# alexandru_ariton.net
KiCad netlist of a schematic drawn in EAGLE
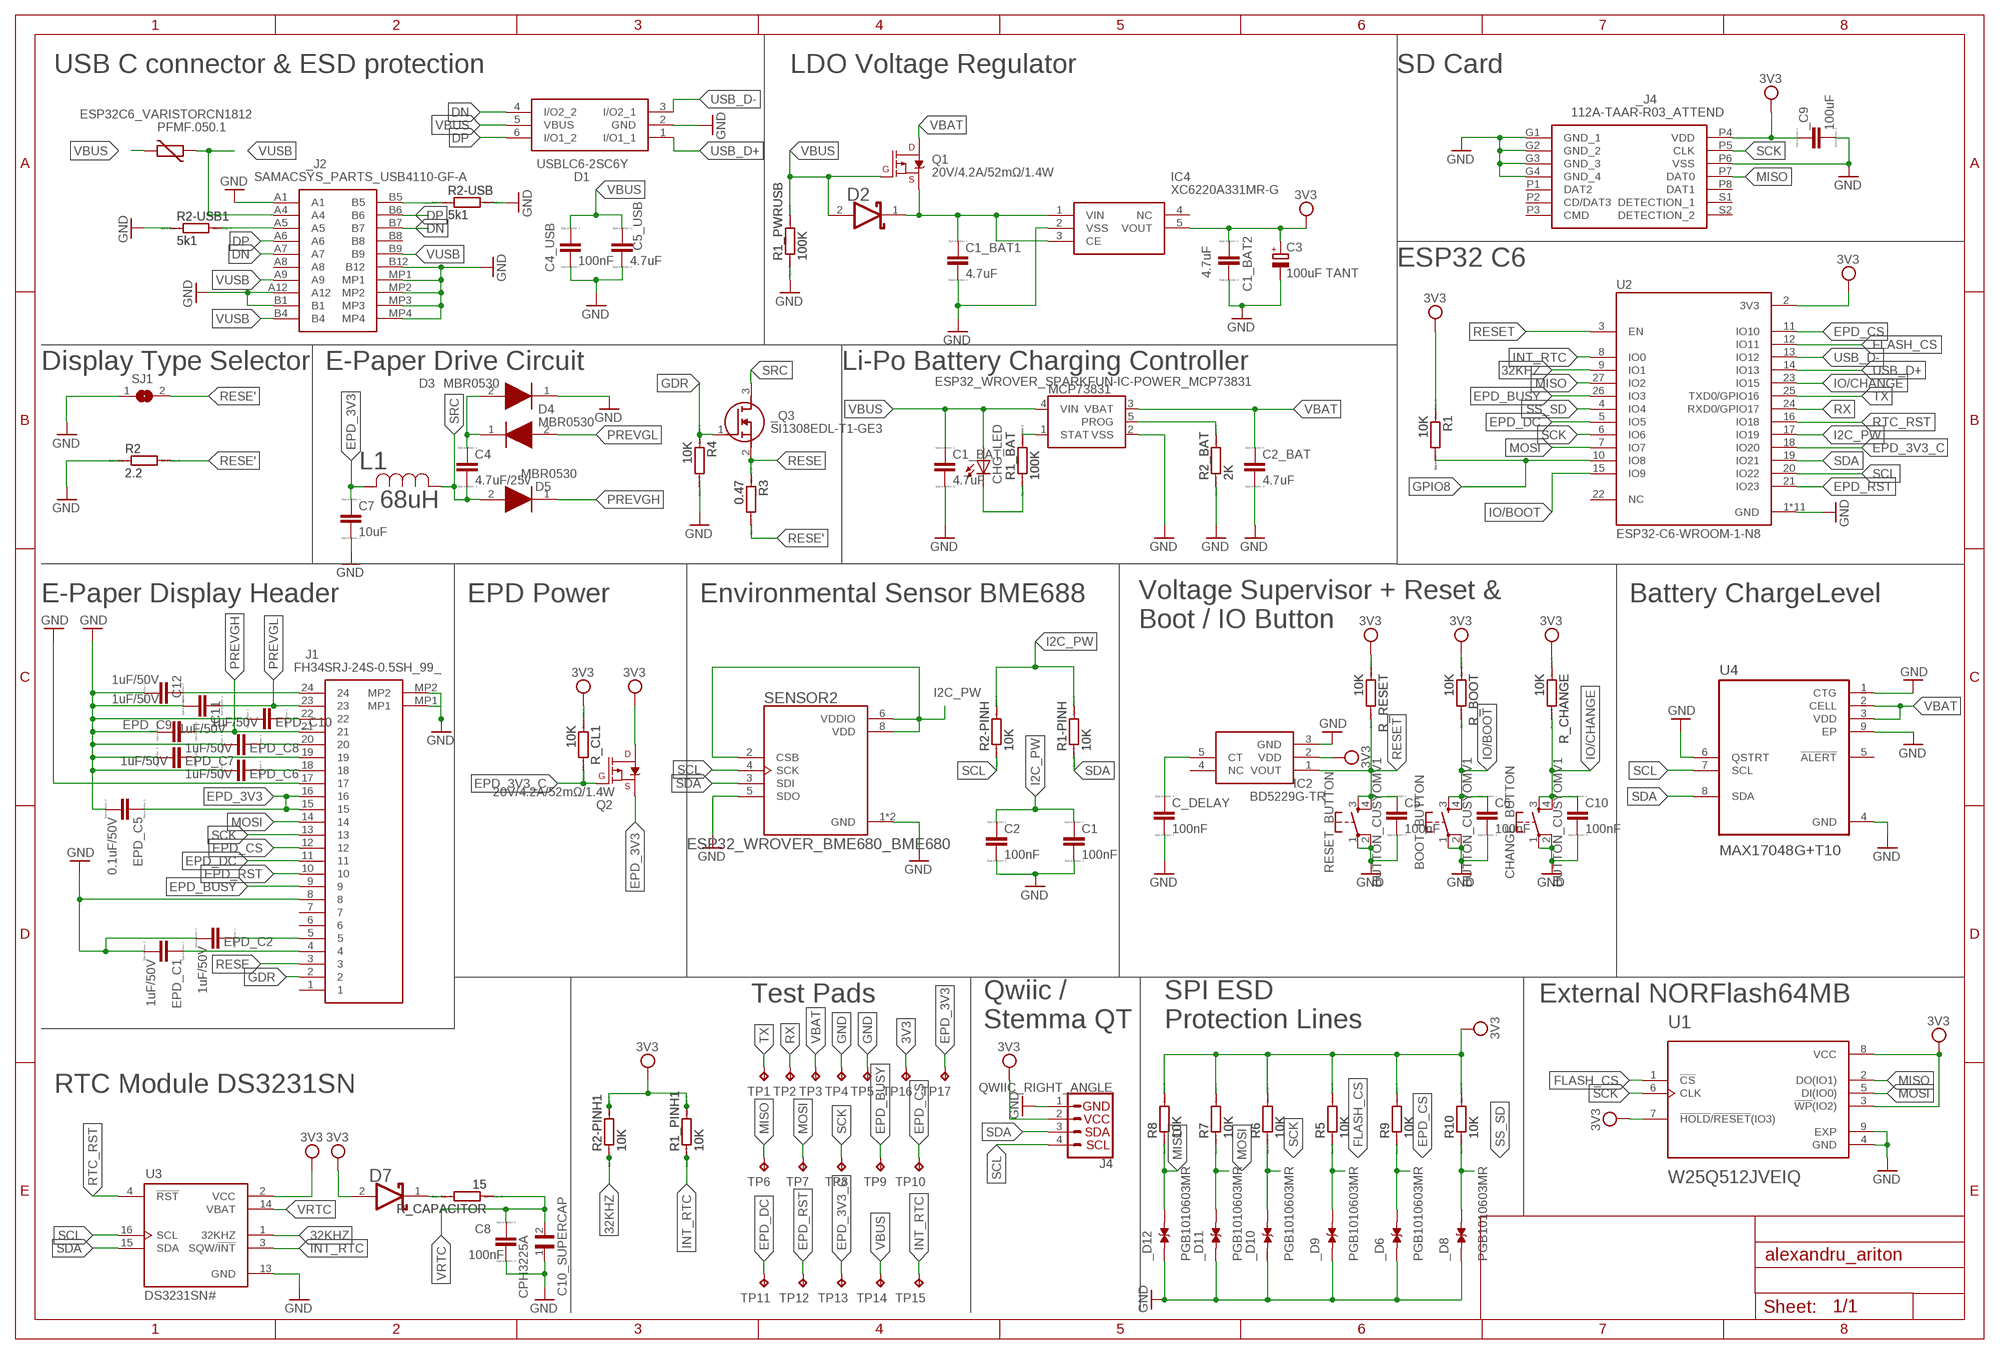
[diagram p0: schematic, sheet 1]

(export (version "E")
  (design (tool "Eeschema 10.0.6"))
  (components
    (comp (ref "BOOT_BUTTON")
      (value "BUTTON_CUSYOMV1")
      (footprint "eagle-import:MYBUTTON")
      (libsource (lib "eagle-import") (part "BUTTON_CUSYOMV1"))
    )
    (comp (ref "C1")
      (value "100nF")
      (footprint "eagle-import:EAGLE-LTSPICE_C0402")
      (libsource (lib "eagle-import") (part "EAGLE-LTSPICE_CC0402"))
    )
    (comp (ref "C1_BAT")
      (value "4.7uF")
      (footprint "eagle-import:EAGLE-LTSPICE_C0402")
      (libsource (lib "eagle-import") (part "EAGLE-LTSPICE_CC0402"))
    )
    (comp (ref "C1_BAT1")
      (value "4.7uF")
      (footprint "eagle-import:EAGLE-LTSPICE_C0402")
      (libsource (lib "eagle-import") (part "EAGLE-LTSPICE_CC0402"))
    )
    (comp (ref "C1_BAT2")
      (value "4.7uF")
      (footprint "eagle-import:EAGLE-LTSPICE_C0402")
      (libsource (lib "eagle-import") (part "EAGLE-LTSPICE_CC0402"))
    )
    (comp (ref "C2")
      (value "100nF")
      (footprint "eagle-import:EAGLE-LTSPICE_C0402")
      (libsource (lib "eagle-import") (part "EAGLE-LTSPICE_CC0402"))
    )
    (comp (ref "C2_BAT")
      (value "4.7uF")
      (footprint "eagle-import:EAGLE-LTSPICE_C0402")
      (libsource (lib "eagle-import") (part "EAGLE-LTSPICE_CC0402"))
    )
    (comp (ref "C3")
      (value "100uF TANT")
      (footprint "eagle-import:RCL_CT3528")
      (libsource (lib "eagle-import") (part "RCL_CPOL-EUCT3528"))
    )
    (comp (ref "C4")
      (value "4.7uF/25v")
      (footprint "eagle-import:EAGLE-LTSPICE_C0402")
      (libsource (lib "eagle-import") (part "EAGLE-LTSPICE_CC0402"))
    )
    (comp (ref "C4_USB")
      (value "100nF")
      (footprint "eagle-import:EAGLE-LTSPICE_C0402")
      (libsource (lib "eagle-import") (part "EAGLE-LTSPICE_CC0402"))
    )
    (comp (ref "C5")
      (value "100nF")
      (footprint "eagle-import:ESP32_WROVER_EAGLE-LTSPICE_C0402")
      (libsource (lib "eagle-import") (part "ESP32_WROVER_EAGLE-LTSPICE_CC0402"))
    )
    (comp (ref "C5_USB")
      (value "4.7uF")
      (footprint "eagle-import:EAGLE-LTSPICE_C0402")
      (libsource (lib "eagle-import") (part "EAGLE-LTSPICE_CC0402"))
    )
    (comp (ref "C6")
      (value "100nF")
      (footprint "eagle-import:ESP32_WROVER_EAGLE-LTSPICE_C0402")
      (libsource (lib "eagle-import") (part "ESP32_WROVER_EAGLE-LTSPICE_CC0402"))
    )
    (comp (ref "C7")
      (value "10uF")
      (footprint "eagle-import:EAGLE-LTSPICE_C0402")
      (libsource (lib "eagle-import") (part "EAGLE-LTSPICE_CC0402"))
    )
    (comp (ref "C8")
      (value "100nF")
      (footprint "eagle-import:EAGLE-LTSPICE_C0402")
      (libsource (lib "eagle-import") (part "EAGLE-LTSPICE_CC0402"))
    )
    (comp (ref "C10")
      (value "100nF")
      (footprint "eagle-import:ESP32_WROVER_EAGLE-LTSPICE_C0402")
      (libsource (lib "eagle-import") (part "ESP32_WROVER_EAGLE-LTSPICE_CC0402"))
    )
    (comp (ref "C10_SUPERCAP")
      (value "CPH3225A")
      (footprint "eagle-import:CAPCP3225X100N")
      (fields (field (name "MF") "Seiko Instruments"))
      (libsource (lib "eagle-import") (part "CPH3225A"))
    )
    (comp (ref "C11")
      (value "1uF/50V")
      (footprint "eagle-import:EAGLE-LTSPICE_C0402")
      (libsource (lib "eagle-import") (part "EAGLE-LTSPICE_CC0402"))
    )
    (comp (ref "C12")
      (value "1uF/50V")
      (footprint "eagle-import:EAGLE-LTSPICE_C0402")
      (libsource (lib "eagle-import") (part "EAGLE-LTSPICE_CC0402"))
    )
    (comp (ref "CHANGE_BUTTON")
      (value "BUTTON_CUSYOMV1")
      (footprint "eagle-import:MYBUTTON")
      (libsource (lib "eagle-import") (part "BUTTON_CUSYOMV1"))
    )
    (comp (ref "CHG_LED")
      (value "ADAFRUIT_LEDCHIP-LED0603")
      (footprint "eagle-import:ADAFRUIT_CHIP-LED0603")
      (libsource (lib "eagle-import") (part "ADAFRUIT_LEDCHIP-LED0603"))
    )
    (comp (ref "C_DELAY")
      (value "100nF")
      (footprint "eagle-import:ESP32_WROVER_EAGLE-LTSPICE_C0402")
      (libsource (lib "eagle-import") (part "ESP32_WROVER_EAGLE-LTSPICE_CC0402"))
    )
    (comp (ref "D1")
      (value "USBLC6-2SC6Y")
      (footprint "eagle-import:SOT95P280X145-6N")
      (fields (field (name "MF") "STMicroelectronics"))
      (libsource (lib "eagle-import") (part "USBLC6-2SC6Y"))
    )
    (comp (ref "D2")
      (value "ESP32_WROVER_AVX---SD0805S020S1R0_AVX_SD0805S020S1R0_0_0AVX_SD0805S020S1R0_0_0")
      (footprint "eagle-import:ESP32_WROVER_AVX---SD0805S020S1R0_AVX_SD0805S020S1R0_0")
      (fields
        (field (name "DIGIKEY_PART_NUMBER") "478-7800-1-ND")
        (field (name "MF") "AVX")
        (field (name "MOUSER_PART_NUMBER") "581-SD0805S020S1R0")
      )
      (libsource (lib "eagle-import") (part "ESP32_WROVER_AVX---SD0805S020S1R0_AVX_SD0805S020S1R0_0_0AVX_SD0805S020S1R0_0_0"))
    )
    (comp (ref "D3")
      (value "MBR0530")
      (footprint "eagle-import:SOD3716X135N")
      (fields (field (name "MF") "ON Semiconductor"))
      (libsource (lib "eagle-import") (part "MBR0530"))
    )
    (comp (ref "D4")
      (value "MBR0530")
      (footprint "eagle-import:SOD3716X135N")
      (fields (field (name "MF") "ON Semiconductor"))
      (libsource (lib "eagle-import") (part "MBR0530"))
    )
    (comp (ref "D5")
      (value "MBR0530")
      (footprint "eagle-import:SOD3716X135N")
      (fields (field (name "MF") "ON Semiconductor"))
      (libsource (lib "eagle-import") (part "MBR0530"))
    )
    (comp (ref "D7")
      (value "ESP32_WROVER_AVX---SD0805S020S1R0_AVX_SD0805S020S1R0_0_0AVX_SD0805S020S1R0_0_0")
      (footprint "eagle-import:ESP32_WROVER_AVX---SD0805S020S1R0_AVX_SD0805S020S1R0_0")
      (fields
        (field (name "DIGIKEY_PART_NUMBER") "478-7800-1-ND")
        (field (name "MF") "AVX")
        (field (name "MOUSER_PART_NUMBER") "581-SD0805S020S1R0")
      )
      (libsource (lib "eagle-import") (part "ESP32_WROVER_AVX---SD0805S020S1R0_AVX_SD0805S020S1R0_0_0AVX_SD0805S020S1R0_0_0"))
    )
    (comp (ref "EPD_C1")
      (value "1uF/50V")
      (footprint "eagle-import:EAGLE-LTSPICE_C0402")
      (libsource (lib "eagle-import") (part "EAGLE-LTSPICE_CC0402"))
    )
    (comp (ref "EPD_C2")
      (value "1uF/50V")
      (footprint "eagle-import:EAGLE-LTSPICE_C0402")
      (libsource (lib "eagle-import") (part "EAGLE-LTSPICE_CC0402"))
    )
    (comp (ref "EPD_C5")
      (value "0.1uF/50V")
      (footprint "eagle-import:EAGLE-LTSPICE_C0402")
      (libsource (lib "eagle-import") (part "EAGLE-LTSPICE_CC0402"))
    )
    (comp (ref "EPD_C6")
      (value "1uF/50V")
      (footprint "eagle-import:EAGLE-LTSPICE_C0402")
      (libsource (lib "eagle-import") (part "EAGLE-LTSPICE_CC0402"))
    )
    (comp (ref "EPD_C7")
      (value "1uF/50V")
      (footprint "eagle-import:EAGLE-LTSPICE_C0402")
      (libsource (lib "eagle-import") (part "EAGLE-LTSPICE_CC0402"))
    )
    (comp (ref "EPD_C8")
      (value "1uF/50V")
      (footprint "eagle-import:EAGLE-LTSPICE_C0402")
      (libsource (lib "eagle-import") (part "EAGLE-LTSPICE_CC0402"))
    )
    (comp (ref "EPD_C9")
      (value "1uF/50V")
      (footprint "eagle-import:EAGLE-LTSPICE_C0402")
      (libsource (lib "eagle-import") (part "EAGLE-LTSPICE_CC0402"))
    )
    (comp (ref "EPD_C10")
      (value "1uF/50V")
      (footprint "eagle-import:EAGLE-LTSPICE_C0402")
      (libsource (lib "eagle-import") (part "EAGLE-LTSPICE_CC0402"))
    )
    (comp (ref "IC2")
      (value "BD5229G-TR")
      (footprint "eagle-import:SOT95P280X125-5N")
      (fields (field (name "MOUSER_PART_NUMBER") "755-BD5229G-TR"))
      (libsource (lib "eagle-import") (part "BD5229G-TR"))
    )
    (comp (ref "IC4")
      (value "XC6220A331MR-G")
      (footprint "eagle-import:SOT95P280X120-5N")
      (fields (field (name "MOUSER_PART_NUMBER") "865-XC6220A331MR-G"))
      (libsource (lib "eagle-import") (part "XC6220A331MR-G"))
    )
    (comp (ref "J1")
      (value "FH34SRJ-24S-0.5SH_99_")
      (footprint "eagle-import:FH34SRJ24S05SH99")
      (fields
        (field (name "MANUFACTURER_PART_NUMBER") "FH34SRJ-24S-0.5SH(99)")
        (field (name "MOUSER_PART_NUMBER") "798-FH34SRJ24S05SH99")
      )
      (libsource (lib "eagle-import") (part "FH34SRJ-24S-0.5SH_99_"))
    )
    (comp (ref "J4")
      (value "QWIIC_RIGHT_ANGLE")
      (footprint "eagle-import:JST04_1MM_RA")
      (libsource (lib "eagle-import") (part "QWIIC_CONNECTORJS-1MM"))
    )
    (comp (ref "L1")
      (value "68uH")
      (footprint "eagle-import:IND_4828-WE-TPC_WRE")
      (fields
        (field (name "MANUFACTURER_PART_NUMBER") "744043680")
        (field (name "COPYRIGHT") "Copyright (C) 2024 Ultra Librarian. All rights reserved.")
      )
      (libsource (lib "eagle-import") (part "744043680IND_4828-WE-TPC_WRE"))
    )
    (comp (ref "MCP73831")
      (value "ESP32_WROVER_SPARKFUN-IC-POWER_MCP73831")
      (footprint "eagle-import:ESP32_WROVER_SPARKFUN-IC-POWER_SOT23-5")
      (libsource (lib "eagle-import") (part "ESP32_WROVER_SPARKFUN-IC-POWER_MCP73831"))
    )
    (comp (ref "PFMF.050.1")
      (value "ESP32C6_VARISTORCN1812")
      (footprint "eagle-import:ESP32C6_VARISTOR_CT_CN1812")
      (libsource (lib "eagle-import") (part "ESP32C6_VARISTORCN1812"))
    )
    (comp (ref "Q1")
      (value "20V/4.2A/52mΩ/1.4W")
      (footprint "eagle-import:ESP32_WROVER_SPARKFUN-DISCRETESEMI_SOT23-3")
      (libsource (lib "eagle-import") (part "ESP32_WROVER_SPARKFUN-DISCRETESEMI_MOSFET_PCH-DMG2305UX-7"))
    )
    (comp (ref "Q2")
      (value "20V/4.2A/52mΩ/1.4W")
      (footprint "eagle-import:ESP32_WROVER_SPARKFUN-DISCRETESEMI_SOT23-3")
      (libsource (lib "eagle-import") (part "ESP32_WROVER_SPARKFUN-DISCRETESEMI_MOSFET_PCH-DMG2305UX-7"))
    )
    (comp (ref "R1")
      (value "10K")
      (footprint "eagle-import:ESP32_WROVER_EAGLE-LTSPICE_R0402")
      (libsource (lib "eagle-import") (part "ESP32_WROVER_EAGLE-LTSPICE_RR0402"))
    )
    (comp (ref "R1-PINH")
      (value "10K")
      (footprint "eagle-import:ESP32_WROVER_EAGLE-LTSPICE_R0402")
      (libsource (lib "eagle-import") (part "ESP32_WROVER_EAGLE-LTSPICE_RR0402"))
    )
    (comp (ref "R1_BAT")
      (value "100K")
      (footprint "eagle-import:ESP32_WROVER_EAGLE-LTSPICE_R0402")
      (libsource (lib "eagle-import") (part "ESP32_WROVER_EAGLE-LTSPICE_RR0402"))
    )
    (comp (ref "R1_PINH1")
      (value "10K")
      (footprint "eagle-import:ESP32_WROVER_EAGLE-LTSPICE_R0402")
      (libsource (lib "eagle-import") (part "ESP32_WROVER_EAGLE-LTSPICE_RR0402"))
    )
    (comp (ref "R1_PWRUSB")
      (value "100K")
      (footprint "eagle-import:ESP32_WROVER_EAGLE-LTSPICE_R0402")
      (libsource (lib "eagle-import") (part "ESP32_WROVER_EAGLE-LTSPICE_RR0402"))
    )
    (comp (ref "R2")
      (value "2.2")
      (footprint "eagle-import:ESP32_WROVER_EAGLE-LTSPICE_R0402")
      (libsource (lib "eagle-import") (part "ESP32_WROVER_EAGLE-LTSPICE_RR0402"))
    )
    (comp (ref "R2-PINH")
      (value "10K")
      (footprint "eagle-import:ESP32_WROVER_EAGLE-LTSPICE_R0402")
      (libsource (lib "eagle-import") (part "ESP32_WROVER_EAGLE-LTSPICE_RR0402"))
    )
    (comp (ref "R2-PINH1")
      (value "10K")
      (footprint "eagle-import:ESP32_WROVER_EAGLE-LTSPICE_R0402")
      (libsource (lib "eagle-import") (part "ESP32_WROVER_EAGLE-LTSPICE_RR0402"))
    )
    (comp (ref "R2-USB")
      (value "5k1")
      (footprint "eagle-import:ESP32_WROVER_EAGLE-LTSPICE_R0402")
      (libsource (lib "eagle-import") (part "ESP32_WROVER_EAGLE-LTSPICE_RR0402"))
    )
    (comp (ref "R2-USB1")
      (value "5k1")
      (footprint "eagle-import:ESP32_WROVER_EAGLE-LTSPICE_R0402")
      (libsource (lib "eagle-import") (part "ESP32_WROVER_EAGLE-LTSPICE_RR0402"))
    )
    (comp (ref "R2_BAT")
      (value "2K")
      (footprint "eagle-import:ESP32_WROVER_EAGLE-LTSPICE_R0402")
      (libsource (lib "eagle-import") (part "ESP32_WROVER_EAGLE-LTSPICE_RR0402"))
    )
    (comp (ref "R3")
      (value "0.47")
      (footprint "eagle-import:ESP32_WROVER_EAGLE-LTSPICE_R0402")
      (libsource (lib "eagle-import") (part "ESP32_WROVER_EAGLE-LTSPICE_RR0402"))
    )
    (comp (ref "R4")
      (value "10K")
      (footprint "eagle-import:ESP32_WROVER_EAGLE-LTSPICE_R0402")
      (libsource (lib "eagle-import") (part "ESP32_WROVER_EAGLE-LTSPICE_RR0402"))
    )
    (comp (ref "R5")
      (value "10K")
      (footprint "eagle-import:ESP32_WROVER_EAGLE-LTSPICE_R0402")
      (libsource (lib "eagle-import") (part "ESP32_WROVER_EAGLE-LTSPICE_RR0402"))
    )
    (comp (ref "R6")
      (value "10K")
      (footprint "eagle-import:ESP32_WROVER_EAGLE-LTSPICE_R0402")
      (libsource (lib "eagle-import") (part "ESP32_WROVER_EAGLE-LTSPICE_RR0402"))
    )
    (comp (ref "R7")
      (value "10K")
      (footprint "eagle-import:ESP32_WROVER_EAGLE-LTSPICE_R0402")
      (libsource (lib "eagle-import") (part "ESP32_WROVER_EAGLE-LTSPICE_RR0402"))
    )
    (comp (ref "R8")
      (value "10K")
      (footprint "eagle-import:ESP32_WROVER_EAGLE-LTSPICE_R0402")
      (libsource (lib "eagle-import") (part "ESP32_WROVER_EAGLE-LTSPICE_RR0402"))
    )
    (comp (ref "R9")
      (value "10K")
      (footprint "eagle-import:ESP32_WROVER_EAGLE-LTSPICE_R0402")
      (libsource (lib "eagle-import") (part "ESP32_WROVER_EAGLE-LTSPICE_RR0402"))
    )
    (comp (ref "R10")
      (value "10K")
      (footprint "eagle-import:ESP32_WROVER_EAGLE-LTSPICE_R0402")
      (libsource (lib "eagle-import") (part "ESP32_WROVER_EAGLE-LTSPICE_RR0402"))
    )
    (comp (ref "RESET_BUTTON")
      (value "BUTTON_CUSYOMV1")
      (footprint "eagle-import:MYBUTTON")
      (libsource (lib "eagle-import") (part "BUTTON_CUSYOMV1"))
    )
    (comp (ref "R_BOOT")
      (value "10K")
      (footprint "eagle-import:ESP32_WROVER_EAGLE-LTSPICE_R0402")
      (libsource (lib "eagle-import") (part "ESP32_WROVER_EAGLE-LTSPICE_RR0402"))
    )
    (comp (ref "R_CAPACITOR")
      (value "15")
      (footprint "eagle-import:ESP32_WROVER_EAGLE-LTSPICE_R0402")
      (libsource (lib "eagle-import") (part "ESP32_WROVER_EAGLE-LTSPICE_RR0402"))
    )
    (comp (ref "R_CHANGE")
      (value "10K")
      (footprint "eagle-import:ESP32_WROVER_EAGLE-LTSPICE_R0402")
      (libsource (lib "eagle-import") (part "ESP32_WROVER_EAGLE-LTSPICE_RR0402"))
    )
    (comp (ref "R_CL1")
      (value "10K")
      (footprint "eagle-import:ESP32_WROVER_EAGLE-LTSPICE_R0402")
      (libsource (lib "eagle-import") (part "ESP32_WROVER_EAGLE-LTSPICE_RR0402"))
    )
    (comp (ref "R_RESET")
      (value "10K")
      (footprint "eagle-import:ESP32_WROVER_EAGLE-LTSPICE_R0402")
      (libsource (lib "eagle-import") (part "ESP32_WROVER_EAGLE-LTSPICE_RR0402"))
    )
    (comp (ref "SENSOR2")
      (value "ESP32_WROVER_BME680_BME680")
      (footprint "eagle-import:ESP32_WROVER_BME680_PSON80P300X300X100-8N")
      (fields (field (name "MF") "Bosch Sensortec") (field (name "MP") "BME680"))
      (libsource (lib "eagle-import") (part "ESP32_WROVER_BME680_BME680"))
    )
    (comp (ref "SJ1") (value "SJ") (footprint "eagle-import:SJ") (libsource (lib "eagle-import") (part "SJ")))
    (comp (ref "TP1")
      (value "TPTP20R")
      (footprint "eagle-import:TP20R")
      (libsource (lib "eagle-import") (part "TPTP20R"))
    )
    (comp (ref "TP2")
      (value "TPTP20R")
      (footprint "eagle-import:TP20R")
      (libsource (lib "eagle-import") (part "TPTP20R"))
    )
    (comp (ref "TP3")
      (value "TPTP20R")
      (footprint "eagle-import:TP20R")
      (libsource (lib "eagle-import") (part "TPTP20R"))
    )
    (comp (ref "TP4")
      (value "TPTP20R")
      (footprint "eagle-import:TP20R")
      (libsource (lib "eagle-import") (part "TPTP20R"))
    )
    (comp (ref "TP5")
      (value "TPTP20R")
      (footprint "eagle-import:TP20R")
      (libsource (lib "eagle-import") (part "TPTP20R"))
    )
    (comp (ref "TP6")
      (value "TPTP20R")
      (footprint "eagle-import:TP20R")
      (libsource (lib "eagle-import") (part "TPTP20R"))
    )
    (comp (ref "TP7")
      (value "TPTP20R")
      (footprint "eagle-import:TP20R")
      (libsource (lib "eagle-import") (part "TPTP20R"))
    )
    (comp (ref "TP8")
      (value "TPTP20R")
      (footprint "eagle-import:TP20R")
      (libsource (lib "eagle-import") (part "TPTP20R"))
    )
    (comp (ref "TP9")
      (value "TPTP20R")
      (footprint "eagle-import:TP20R")
      (libsource (lib "eagle-import") (part "TPTP20R"))
    )
    (comp (ref "TP10")
      (value "TPTP20R")
      (footprint "eagle-import:TP20R")
      (libsource (lib "eagle-import") (part "TPTP20R"))
    )
    (comp (ref "TP11")
      (value "TPTP20R")
      (footprint "eagle-import:TP20R")
      (libsource (lib "eagle-import") (part "TPTP20R"))
    )
    (comp (ref "TP12")
      (value "TPTP20R")
      (footprint "eagle-import:TP20R")
      (libsource (lib "eagle-import") (part "TPTP20R"))
    )
    (comp (ref "TP13")
      (value "TPTP20R")
      (footprint "eagle-import:TP20R")
      (libsource (lib "eagle-import") (part "TPTP20R"))
    )
    (comp (ref "TP14")
      (value "TPTP20R")
      (footprint "eagle-import:TP20R")
      (libsource (lib "eagle-import") (part "TPTP20R"))
    )
    (comp (ref "TP15")
      (value "TPTP20R")
      (footprint "eagle-import:TP20R")
      (libsource (lib "eagle-import") (part "TPTP20R"))
    )
    (comp (ref "TP16")
      (value "TPTP20R")
      (footprint "eagle-import:TP20R")
      (libsource (lib "eagle-import") (part "TPTP20R"))
    )
    (comp (ref "TP17")
      (value "TPTP20R")
      (footprint "eagle-import:TP20R")
      (libsource (lib "eagle-import") (part "TPTP20R"))
    )
    (comp (ref "U1")
      (value "W25Q512JVEIQ")
      (footprint "eagle-import:SON127P600X800X80-9N")
      (fields (field (name "MF") "Winbond Electronics"))
      (libsource (lib "eagle-import") (part "W25Q512JVEIQ"))
    )
    (comp (ref "U2")
      (value "ESP32-C6-WROOM-1-N8")
      (footprint "eagle-import:XCVR_ESP32-C6-WROOM-1-N8")
      (fields (field (name "MF") "Espressif Systems"))
      (libsource (lib "eagle-import") (part "ESP32-C6-WROOM-1-N8"))
    )
    (comp (ref "U3")
      (value "DS3231SN#")
      (footprint "eagle-import:SOIC127P1032X265-16N")
      (fields (field (name "MF") "Analog Devices"))
      (libsource (lib "eagle-import") (part "DS3231SN#"))
    )
    (comp (ref "U4")
      (value "MAX17048G+T10")
      (footprint "eagle-import:SON50P200X200X80-9N")
      (fields (field (name "MF") "Analog Devices"))
      (libsource (lib "eagle-import") (part "MAX17048G+T10"))
    )
    (comp (ref "_C9")
      (value "100uF")
      (footprint "eagle-import:EAGLE-LTSPICE_C0402")
      (libsource (lib "eagle-import") (part "EAGLE-LTSPICE_CC0402"))
    )
    (comp (ref "_D6")
      (value "PGB1010603MR")
      (footprint "eagle-import:DIOC1608X36N")
      (fields (field (name "MF") "Littelfuse Inc."))
      (libsource (lib "eagle-import") (part "PGB1010603MR"))
    )
    (comp (ref "_D8")
      (value "PGB1010603MR")
      (footprint "eagle-import:DIOC1608X36N")
      (fields (field (name "MF") "Littelfuse Inc."))
      (libsource (lib "eagle-import") (part "PGB1010603MR"))
    )
    (comp (ref "_D9")
      (value "PGB1010603MR")
      (footprint "eagle-import:DIOC1608X36N")
      (fields (field (name "MF") "Littelfuse Inc."))
      (libsource (lib "eagle-import") (part "PGB1010603MR"))
    )
    (comp (ref "_D10")
      (value "PGB1010603MR")
      (footprint "eagle-import:DIOC1608X36N")
      (fields (field (name "MF") "Littelfuse Inc."))
      (libsource (lib "eagle-import") (part "PGB1010603MR"))
    )
    (comp (ref "_D11")
      (value "PGB1010603MR")
      (footprint "eagle-import:DIOC1608X36N")
      (fields (field (name "MF") "Littelfuse Inc."))
      (libsource (lib "eagle-import") (part "PGB1010603MR"))
    )
    (comp (ref "_D12")
      (value "PGB1010603MR")
      (footprint "eagle-import:DIOC1608X36N")
      (fields (field (name "MF") "Littelfuse Inc."))
      (libsource (lib "eagle-import") (part "PGB1010603MR"))
    )
    (comp (ref "_J2")
      (value "SAMACSYS_PARTS_USB4110-GF-A")
      (footprint "eagle-import:SAMACSYS_PARTS_USB4110GFA")
      (fields
        (field (name "MANUFACTURER_PART_NUMBER") "USB4110-GF-A")
        (field (name "MOUSER_PART_NUMBER") "640-USB4110-GF-A")
      )
      (libsource (lib "eagle-import") (part "SAMACSYS_PARTS_USB4110-GF-A"))
    )
    (comp (ref "_J4")
      (value "112A-TAAR-R03_ATTEND")
      (footprint "eagle-import:112ATAARR03ATTEND")
      (fields (field (name "MANUFACTURER_PART_NUMBER") "112A-TAAR-R03 ATTEND"))
      (libsource (lib "eagle-import") (part "112A-TAAR-R03_ATTEND"))
    )
    (comp (ref "_Q3")
      (value "SI1308EDL-T1-GE3")
      (footprint "eagle-import:SOT65P210X110-3N")
      (fields (field (name "MF") "Vishay Siliconix"))
      (libsource (lib "eagle-import") (part "SI1308EDL-T1-GE3"))
    )
  )
  (nets
    (net (code "1") (name "3V3") (class "Default")
      (node (ref "C1_BAT2") (pin "1") (pinfunction "1_1") (pintype "passive"))
      (node (ref "C3") (pin "+") (pinfunction "+_+") (pintype "passive"))
      (node (ref "D7") (pin "2") (pinfunction "ANODE_2") (pintype "bidirectional"))
      (node (ref "IC2") (pin "2") (pinfunction "VDD_2") (pintype "bidirectional"))
      (node (ref "IC4") (pin "5") (pinfunction "VOUT_5") (pintype "bidirectional"))
      (node (ref "J4") (pin "2") (pinfunction "2_2") (pintype "power_in"))
      (node (ref "Q2") (pin "3") (pinfunction "D_3") (pintype "bidirectional"))
      (node (ref "R1") (pin "1") (pinfunction "1_1") (pintype "passive"))
      (node (ref "R10") (pin "2") (pinfunction "2_2") (pintype "passive"))
      (node (ref "R1_PINH1") (pin "2") (pinfunction "2_2") (pintype "passive"))
      (node (ref "R2-PINH1") (pin "2") (pinfunction "2_2") (pintype "passive"))
      (node (ref "R5") (pin "2") (pinfunction "2_2") (pintype "passive"))
      (node (ref "R6") (pin "2") (pinfunction "2_2") (pintype "passive"))
      (node (ref "R7") (pin "2") (pinfunction "2_2") (pintype "passive"))
      (node (ref "R8") (pin "2") (pinfunction "2_2") (pintype "passive"))
      (node (ref "R9") (pin "2") (pinfunction "2_2") (pintype "passive"))
      (node (ref "R_BOOT") (pin "1") (pinfunction "1_1") (pintype "passive"))
      (node (ref "R_CHANGE") (pin "1") (pinfunction "1_1") (pintype "passive"))
      (node (ref "R_CL1") (pin "1") (pinfunction "1_1") (pintype "passive"))
      (node (ref "R_RESET") (pin "1") (pinfunction "1_1") (pintype "passive"))
      (node (ref "TP16") (pin "TP") (pinfunction "TP_TP") (pintype "input"))
      (node (ref "U1") (pin "3") (pinfunction "~{WP}(IO2)_3") (pintype "bidirectional"))
      (node (ref "U1") (pin "7") (pinfunction "~{HOLD}/~{RESET}(IO3)_7") (pintype "bidirectional"))
      (node (ref "U1") (pin "8") (pinfunction "VCC_8") (pintype "power_in"))
      (node (ref "U2") (pin "2") (pinfunction "3V3_2") (pintype "power_in"))
      (node (ref "U3") (pin "2") (pinfunction "VCC_2") (pintype "power_in"))
      (node (ref "_C9") (pin "1") (pinfunction "1_1") (pintype "passive"))
      (node (ref "_J4") (pin "P4") (pinfunction "VDD_P4") (pintype "bidirectional"))
    )
    (net (code "2") (name "32KHZ") (class "Default")
      (node (ref "R2-PINH1") (pin "1") (pinfunction "1_1") (pintype "passive"))
      (node (ref "U2") (pin "9") (pinfunction "IO1_9") (pintype "bidirectional"))
      (node (ref "U3") (pin "1") (pinfunction "32KHZ_1") (pintype "output"))
    )
    (net (code "3") (name "DN") (class "Default")
      (node (ref "D1") (pin "4") (pinfunction "I/O2_2_4") (pintype "bidirectional"))
      (node (ref "_J2") (pin "A7") (pinfunction "A7_A7") (pintype "bidirectional"))
      (node (ref "_J2") (pin "B7") (pinfunction "B7_B7") (pintype "bidirectional"))
    )
    (net (code "4") (name "DP") (class "Default")
      (node (ref "D1") (pin "6") (pinfunction "I/O1_2_6") (pintype "bidirectional"))
      (node (ref "_J2") (pin "A6") (pinfunction "A6_A6") (pintype "bidirectional"))
      (node (ref "_J2") (pin "B6") (pinfunction "B6_B6") (pintype "bidirectional"))
    )
    (net (code "5") (name "EPD_3V3") (class "Default")
      (node (ref "C7") (pin "1") (pinfunction "1_1") (pintype "passive"))
      (node (ref "EPD_C5") (pin "1") (pinfunction "1_1") (pintype "passive"))
      (node (ref "J1") (pin "15") (pinfunction "15_15") (pintype "bidirectional"))
      (node (ref "J1") (pin "16") (pinfunction "16_16") (pintype "bidirectional"))
      (node (ref "L1") (pin "2") (pinfunction "2_2") (pintype "passive"))
      (node (ref "Q2") (pin "2") (pinfunction "S_2") (pintype "bidirectional"))
      (node (ref "TP17") (pin "TP") (pinfunction "TP_TP") (pintype "input"))
    )
    (net (code "6") (name "EPD_3V3_C") (class "Default")
      (node (ref "Q2") (pin "1") (pinfunction "G_1") (pintype "bidirectional"))
      (node (ref "R_CL1") (pin "2") (pinfunction "2_2") (pintype "passive"))
      (node (ref "TP13") (pin "TP") (pinfunction "TP_TP") (pintype "input"))
      (node (ref "U2") (pin "18") (pinfunction "IO20_18") (pintype "bidirectional"))
    )
    (net (code "7") (name "EPD_BUSY") (class "Default")
      (node (ref "J1") (pin "9") (pinfunction "9_9") (pintype "bidirectional"))
      (node (ref "TP9") (pin "TP") (pinfunction "TP_TP") (pintype "input"))
      (node (ref "U2") (pin "26") (pinfunction "IO3_26") (pintype "bidirectional"))
    )
    (net (code "8") (name "EPD_CS") (class "Default")
      (node (ref "J1") (pin "12") (pinfunction "12_12") (pintype "bidirectional"))
      (node (ref "R9") (pin "1") (pinfunction "1_1") (pintype "passive"))
      (node (ref "TP10") (pin "TP") (pinfunction "TP_TP") (pintype "input"))
      (node (ref "U2") (pin "11") (pinfunction "IO10_11") (pintype "bidirectional"))
      (node (ref "_D6") (pin "2") (pinfunction "2_2") (pintype "passive"))
    )
    (net (code "9") (name "EPD_DC") (class "Default")
      (node (ref "J1") (pin "11") (pinfunction "11_11") (pintype "bidirectional"))
      (node (ref "TP11") (pin "TP") (pinfunction "TP_TP") (pintype "input"))
      (node (ref "U2") (pin "5") (pinfunction "IO5_5") (pintype "bidirectional"))
    )
    (net (code "10") (name "EPD_RST") (class "Default")
      (node (ref "J1") (pin "10") (pinfunction "10_10") (pintype "bidirectional"))
      (node (ref "TP12") (pin "TP") (pinfunction "TP_TP") (pintype "input"))
      (node (ref "U2") (pin "21") (pinfunction "IO23_21") (pintype "bidirectional"))
    )
    (net (code "11") (name "FLASH_CS") (class "Default")
      (node (ref "R5") (pin "1") (pinfunction "1_1") (pintype "passive"))
      (node (ref "U1") (pin "1") (pinfunction "~{CS}_1") (pintype "input"))
      (node (ref "U2") (pin "12") (pinfunction "IO11_12") (pintype "bidirectional"))
      (node (ref "_D9") (pin "2") (pinfunction "2_2") (pintype "passive"))
    )
    (net (code "12") (name "GDR") (class "Default")
      (node (ref "J1") (pin "2") (pinfunction "2_2") (pintype "bidirectional"))
      (node (ref "R4") (pin "1") (pinfunction "1_1") (pintype "passive"))
      (node (ref "_Q3") (pin "1") (pinfunction "G_1") (pintype "bidirectional"))
    )
    (net (code "13") (name "GND") (class "Default")
      (node (ref "BOOT_BUTTON") (pin "1") (pinfunction "1_1") (pintype "passive"))
      (node (ref "BOOT_BUTTON") (pin "2") (pinfunction "2_2") (pintype "passive"))
      (node (ref "C1") (pin "2") (pinfunction "2_2") (pintype "passive"))
      (node (ref "C10") (pin "2") (pinfunction "2_2") (pintype "passive"))
      (node (ref "C10_SUPERCAP") (pin "1") (pinfunction "1_1") (pintype "passive"))
      (node (ref "C11") (pin "2") (pinfunction "2_2") (pintype "passive"))
      (node (ref "C12") (pin "2") (pinfunction "2_2") (pintype "passive"))
      (node (ref "C1_BAT") (pin "2") (pinfunction "2_2") (pintype "passive"))
      (node (ref "C1_BAT1") (pin "2") (pinfunction "2_2") (pintype "passive"))
      (node (ref "C1_BAT2") (pin "2") (pinfunction "2_2") (pintype "passive"))
      (node (ref "C2") (pin "2") (pinfunction "2_2") (pintype "passive"))
      (node (ref "C2_BAT") (pin "2") (pinfunction "2_2") (pintype "passive"))
      (node (ref "C3") (pin "-") (pinfunction "-_-") (pintype "passive"))
      (node (ref "C4_USB") (pin "2") (pinfunction "2_2") (pintype "passive"))
      (node (ref "C5") (pin "2") (pinfunction "2_2") (pintype "passive"))
      (node (ref "C5_USB") (pin "2") (pinfunction "2_2") (pintype "passive"))
      (node (ref "C6") (pin "2") (pinfunction "2_2") (pintype "passive"))
      (node (ref "C7") (pin "2") (pinfunction "2_2") (pintype "passive"))
      (node (ref "C8") (pin "2") (pinfunction "2_2") (pintype "passive"))
      (node (ref "CHANGE_BUTTON") (pin "1") (pinfunction "1_1") (pintype "passive"))
      (node (ref "CHANGE_BUTTON") (pin "2") (pinfunction "2_2") (pintype "passive"))
      (node (ref "C_DELAY") (pin "2") (pinfunction "2_2") (pintype "passive"))
      (node (ref "D1") (pin "2") (pinfunction "GND_2") (pintype "bidirectional"))
      (node (ref "D3") (pin "1") (pinfunction "K_1") (pintype "bidirectional"))
      (node (ref "EPD_C1") (pin "2") (pinfunction "2_2") (pintype "passive"))
      (node (ref "EPD_C10") (pin "2") (pinfunction "2_2") (pintype "passive"))
      (node (ref "EPD_C2") (pin "2") (pinfunction "2_2") (pintype "passive"))
      (node (ref "EPD_C5") (pin "2") (pinfunction "2_2") (pintype "passive"))
      (node (ref "EPD_C6") (pin "2") (pinfunction "2_2") (pintype "passive"))
      (node (ref "EPD_C7") (pin "2") (pinfunction "2_2") (pintype "passive"))
      (node (ref "EPD_C8") (pin "2") (pinfunction "2_2") (pintype "passive"))
      (node (ref "EPD_C9") (pin "2") (pinfunction "2_2") (pintype "passive"))
      (node (ref "IC2") (pin "3") (pinfunction "GND_3") (pintype "bidirectional"))
      (node (ref "IC4") (pin "2") (pinfunction "VSS_2") (pintype "bidirectional"))
      (node (ref "J1") (pin "17") (pinfunction "17_17") (pintype "bidirectional"))
      (node (ref "J1") (pin "8") (pinfunction "8_8") (pintype "bidirectional"))
      (node (ref "J1") (pin "MP1") (pinfunction "MP1_MP1") (pintype "bidirectional"))
      (node (ref "J1") (pin "MP2") (pinfunction "MP2_MP2") (pintype "bidirectional"))
      (node (ref "J4") (pin "1") (pinfunction "1_1") (pintype "power_in"))
      (node (ref "MCP73831") (pin "2") (pinfunction "VSS_2") (pintype "power_in"))
      (node (ref "R1_PWRUSB") (pin "1") (pinfunction "1_1") (pintype "passive"))
      (node (ref "R2") (pin "1") (pinfunction "1_1") (pintype "passive"))
      (node (ref "R2-USB") (pin "2") (pinfunction "2_2") (pintype "passive"))
      (node (ref "R2-USB1") (pin "1") (pinfunction "1_1") (pintype "passive"))
      (node (ref "R2_BAT") (pin "1") (pinfunction "1_1") (pintype "passive"))
      (node (ref "R4") (pin "2") (pinfunction "2_2") (pintype "passive"))
      (node (ref "RESET_BUTTON") (pin "1") (pinfunction "1_1") (pintype "passive"))
      (node (ref "RESET_BUTTON") (pin "2") (pinfunction "2_2") (pintype "passive"))
      (node (ref "SENSOR2") (pin "1") (pinfunction "GND_1") (pintype "power_in"))
      (node (ref "SENSOR2") (pin "5") (pinfunction "SDO_5") (pintype "bidirectional"))
      (node (ref "SENSOR2") (pin "7") (pinfunction "GND_7") (pintype "power_in"))
      (node (ref "SJ1") (pin "1") (pinfunction "1_1") (pintype "passive"))
      (node (ref "TP4") (pin "TP") (pinfunction "TP_TP") (pintype "input"))
      (node (ref "TP5") (pin "TP") (pinfunction "TP_TP") (pintype "input"))
      (node (ref "U1") (pin "4") (pinfunction "GND_4") (pintype "power_in"))
      (node (ref "U1") (pin "9") (pinfunction "EXP_9") (pintype "passive"))
      (node (ref "U2") (pin "1") (pinfunction "GND_1") (pintype "power_in"))
      (node (ref "U2") (pin "28") (pinfunction "GND_28") (pintype "power_in"))
      (node (ref "U2") (pin "29_1") (pinfunction "GND_29_1") (pintype "power_in"))
      (node (ref "U2") (pin "29_2") (pinfunction "GND_29_2") (pintype "power_in"))
      (node (ref "U2") (pin "29_3") (pinfunction "GND_29_3") (pintype "power_in"))
      (node (ref "U2") (pin "29_4") (pinfunction "GND_29_4") (pintype "power_in"))
      (node (ref "U2") (pin "29_5") (pinfunction "GND_29_5") (pintype "power_in"))
      (node (ref "U2") (pin "29_6") (pinfunction "GND_29_6") (pintype "power_in"))
      (node (ref "U2") (pin "29_7") (pinfunction "GND_29_7") (pintype "power_in"))
      (node (ref "U2") (pin "29_8") (pinfunction "GND_29_8") (pintype "power_in"))
      (node (ref "U2") (pin "29_9") (pinfunction "GND_29_9") (pintype "power_in"))
      (node (ref "U3") (pin "13") (pinfunction "GND_13") (pintype "power_in"))
      (node (ref "U4") (pin "1") (pinfunction "CTG_1") (pintype "power_in"))
      (node (ref "U4") (pin "4") (pinfunction "GND_4") (pintype "power_in"))
      (node (ref "U4") (pin "6") (pinfunction "QSTRT_6") (pintype "input"))
      (node (ref "U4") (pin "9") (pinfunction "EP_9") (pintype "power_in"))
      (node (ref "_C9") (pin "2") (pinfunction "2_2") (pintype "passive"))
      (node (ref "_D10") (pin "1") (pinfunction "1_1") (pintype "passive"))
      (node (ref "_D11") (pin "1") (pinfunction "1_1") (pintype "passive"))
      (node (ref "_D12") (pin "1") (pinfunction "1_1") (pintype "passive"))
      (node (ref "_D6") (pin "1") (pinfunction "1_1") (pintype "passive"))
      (node (ref "_D8") (pin "1") (pinfunction "1_1") (pintype "passive"))
      (node (ref "_D9") (pin "1") (pinfunction "1_1") (pintype "passive"))
      (node (ref "_J2") (pin "A1") (pinfunction "A1_A1") (pintype "bidirectional"))
      (node (ref "_J2") (pin "A12") (pinfunction "A12_A12") (pintype "bidirectional"))
      (node (ref "_J2") (pin "B1") (pinfunction "B1_B1") (pintype "bidirectional"))
      (node (ref "_J2") (pin "B12") (pinfunction "B12_B12") (pintype "bidirectional"))
      (node (ref "_J2") (pin "MP1") (pinfunction "MP1_MP1") (pintype "bidirectional"))
      (node (ref "_J2") (pin "MP2") (pinfunction "MP2_MP2") (pintype "bidirectional"))
      (node (ref "_J2") (pin "MP3") (pinfunction "MP3_MP3") (pintype "bidirectional"))
      (node (ref "_J2") (pin "MP4") (pinfunction "MP4_MP4") (pintype "bidirectional"))
      (node (ref "_J4") (pin "G1") (pinfunction "GND_1_G1") (pintype "bidirectional"))
      (node (ref "_J4") (pin "G2") (pinfunction "GND_2_G2") (pintype "bidirectional"))
      (node (ref "_J4") (pin "G3") (pinfunction "GND_3_G3") (pintype "bidirectional"))
      (node (ref "_J4") (pin "G4") (pinfunction "GND_4_G4") (pintype "bidirectional"))
      (node (ref "_J4") (pin "P6") (pinfunction "VSS_P6") (pintype "bidirectional"))
    )
    (net (code "14") (name "GPIO8") (class "Default")
      (node (ref "R1") (pin "2") (pinfunction "2_2") (pintype "passive"))
      (node (ref "U2") (pin "10") (pinfunction "IO8_10") (pintype "bidirectional"))
    )
    (net (code "15") (name "I2C_PW") (class "Default")
      (node (ref "C1") (pin "1") (pinfunction "1_1") (pintype "passive"))
      (node (ref "C2") (pin "1") (pinfunction "1_1") (pintype "passive"))
      (node (ref "R1-PINH") (pin "2") (pinfunction "2_2") (pintype "passive"))
      (node (ref "R2-PINH") (pin "2") (pinfunction "2_2") (pintype "passive"))
      (node (ref "SENSOR2") (pin "2") (pinfunction "CSB_2") (pintype "input"))
      (node (ref "SENSOR2") (pin "6") (pinfunction "VDDIO_6") (pintype "power_in"))
      (node (ref "SENSOR2") (pin "8") (pinfunction "VDD_8") (pintype "power_in"))
      (node (ref "U2") (pin "17") (pinfunction "IO19_17") (pintype "bidirectional"))
    )
    (net (code "16") (name "INT_RTC") (class "Default")
      (node (ref "R1_PINH1") (pin "1") (pinfunction "1_1") (pintype "passive"))
      (node (ref "TP15") (pin "TP") (pinfunction "TP_TP") (pintype "input"))
      (node (ref "U2") (pin "8") (pinfunction "IO0_8") (pintype "bidirectional"))
      (node (ref "U3") (pin "3") (pinfunction "SQW/~{INT}_3") (pintype "output"))
    )
    (net (code "17") (name "IO{slash}BOOT") (class "Default")
      (node (ref "BOOT_BUTTON") (pin "3") (pinfunction "3_3") (pintype "passive"))
      (node (ref "BOOT_BUTTON") (pin "4") (pinfunction "4_4") (pintype "passive"))
      (node (ref "C6") (pin "1") (pinfunction "1_1") (pintype "passive"))
      (node (ref "R_BOOT") (pin "2") (pinfunction "2_2") (pintype "passive"))
      (node (ref "U2") (pin "15") (pinfunction "IO9_15") (pintype "bidirectional"))
    )
    (net (code "18") (name "IO{slash}CHANGE") (class "Default")
      (node (ref "C10") (pin "1") (pinfunction "1_1") (pintype "passive"))
      (node (ref "CHANGE_BUTTON") (pin "3") (pinfunction "3_3") (pintype "passive"))
      (node (ref "CHANGE_BUTTON") (pin "4") (pinfunction "4_4") (pintype "passive"))
      (node (ref "R_CHANGE") (pin "2") (pinfunction "2_2") (pintype "passive"))
      (node (ref "U2") (pin "23") (pinfunction "IO15_23") (pintype "bidirectional"))
    )
    (net (code "19") (name "MISO") (class "Default")
      (node (ref "R8") (pin "1") (pinfunction "1_1") (pintype "passive"))
      (node (ref "TP6") (pin "TP") (pinfunction "TP_TP") (pintype "input"))
      (node (ref "U1") (pin "2") (pinfunction "DO(IO1)_2") (pintype "bidirectional"))
      (node (ref "U2") (pin "27") (pinfunction "IO2_27") (pintype "bidirectional"))
      (node (ref "_D12") (pin "2") (pinfunction "2_2") (pintype "passive"))
      (node (ref "_J4") (pin "P7") (pinfunction "DAT0_P7") (pintype "bidirectional"))
    )
    (net (code "20") (name "MOSI") (class "Default")
      (node (ref "J1") (pin "14") (pinfunction "14_14") (pintype "bidirectional"))
      (node (ref "R7") (pin "1") (pinfunction "1_1") (pintype "passive"))
      (node (ref "TP7") (pin "TP") (pinfunction "TP_TP") (pintype "input"))
      (node (ref "U1") (pin "5") (pinfunction "DI(IO0)_5") (pintype "bidirectional"))
      (node (ref "U2") (pin "7") (pinfunction "IO7_7") (pintype "bidirectional"))
      (node (ref "_D11") (pin "2") (pinfunction "2_2") (pintype "passive"))
    )
    (net (code "21") (name "Net-(C12-Pad1)") (class "Default")
      (node (ref "C12") (pin "1") (pinfunction "1_1") (pintype "passive"))
      (node (ref "J1") (pin "24") (pinfunction "24_24") (pintype "bidirectional"))
    )
    (net (code "22") (name "Net-(CHG_LED-PadC)") (class "Default")
      (node (ref "CHG_LED") (pin "C") (pinfunction "C_C") (pintype "passive"))
      (node (ref "R1_BAT") (pin "1") (pinfunction "1_1") (pintype "passive"))
    )
    (net (code "23") (name "Net-(D2-CATHODE)") (class "Default")
      (node (ref "C1_BAT1") (pin "1") (pinfunction "1_1") (pintype "passive"))
      (node (ref "D2") (pin "1") (pinfunction "CATHODE_1") (pintype "bidirectional"))
      (node (ref "IC4") (pin "1") (pinfunction "VIN_1") (pintype "bidirectional"))
      (node (ref "IC4") (pin "3") (pinfunction "CE_3") (pintype "bidirectional"))
      (node (ref "Q1") (pin "2") (pinfunction "S_2") (pintype "bidirectional"))
    )
    (net (code "24") (name "Net-(D3-A)") (class "Default")
      (node (ref "C4") (pin "1") (pinfunction "1_1") (pintype "passive"))
      (node (ref "D3") (pin "2") (pinfunction "A_2") (pintype "bidirectional"))
      (node (ref "D4") (pin "1") (pinfunction "K_1") (pintype "bidirectional"))
    )
    (net (code "25") (name "Net-(D7-CATHODE)") (class "Default")
      (node (ref "D7") (pin "1") (pinfunction "CATHODE_1") (pintype "bidirectional"))
      (node (ref "R_CAPACITOR") (pin "2") (pinfunction "2_2") (pintype "passive"))
    )
    (net (code "26") (name "Net-(EPD_C1-Pad1)") (class "Default")
      (node (ref "EPD_C1") (pin "1") (pinfunction "1_1") (pintype "passive"))
      (node (ref "J1") (pin "4") (pinfunction "4_4") (pintype "bidirectional"))
    )
    (net (code "27") (name "Net-(EPD_C2-Pad1)") (class "Default")
      (node (ref "EPD_C2") (pin "1") (pinfunction "1_1") (pintype "passive"))
      (node (ref "J1") (pin "5") (pinfunction "5_5") (pintype "bidirectional"))
    )
    (net (code "28") (name "Net-(EPD_C6-Pad1)") (class "Default")
      (node (ref "EPD_C6") (pin "1") (pinfunction "1_1") (pintype "passive"))
      (node (ref "J1") (pin "18") (pinfunction "18_18") (pintype "bidirectional"))
    )
    (net (code "29") (name "Net-(EPD_C7-Pad1)") (class "Default")
      (node (ref "EPD_C7") (pin "1") (pinfunction "1_1") (pintype "passive"))
      (node (ref "J1") (pin "19") (pinfunction "19_19") (pintype "bidirectional"))
    )
    (net (code "30") (name "Net-(EPD_C8-Pad1)") (class "Default")
      (node (ref "EPD_C8") (pin "1") (pinfunction "1_1") (pintype "passive"))
      (node (ref "J1") (pin "20") (pinfunction "20_20") (pintype "bidirectional"))
    )
    (net (code "31") (name "Net-(EPD_C10-Pad1)") (class "Default")
      (node (ref "EPD_C10") (pin "1") (pinfunction "1_1") (pintype "passive"))
      (node (ref "J1") (pin "22") (pinfunction "22_22") (pintype "bidirectional"))
    )
    (net (code "32") (name "Net-(IC2-CT)") (class "Default")
      (node (ref "C_DELAY") (pin "1") (pinfunction "1_1") (pintype "passive"))
      (node (ref "IC2") (pin "5") (pinfunction "CT_5") (pintype "bidirectional"))
    )
    (net (code "33") (name "Net-(MCP73831-PROG)") (class "Default")
      (node (ref "MCP73831") (pin "5") (pinfunction "PROG_5") (pintype "input"))
      (node (ref "R2_BAT") (pin "2") (pinfunction "2_2") (pintype "passive"))
    )
    (net (code "34") (name "Net-(MCP73831-STAT)") (class "Default")
      (node (ref "MCP73831") (pin "1") (pinfunction "STAT_1") (pintype "output"))
      (node (ref "R1_BAT") (pin "2") (pinfunction "2_2") (pintype "passive"))
    )
    (net (code "35") (name "Net-(R2-USB-Pad1)") (class "Default")
      (node (ref "R2-USB") (pin "1") (pinfunction "1_1") (pintype "passive"))
      (node (ref "_J2") (pin "B5") (pinfunction "B5_B5") (pintype "bidirectional"))
    )
    (net (code "36") (name "Net-(R2-USB1-Pad2)") (class "Default")
      (node (ref "R2-USB1") (pin "2") (pinfunction "2_2") (pintype "passive"))
      (node (ref "_J2") (pin "A5") (pinfunction "A5_A5") (pintype "bidirectional"))
    )
    (net (code "37") (name "PREVGH") (class "Default")
      (node (ref "D5") (pin "1") (pinfunction "K_1") (pintype "bidirectional"))
      (node (ref "EPD_C9") (pin "1") (pinfunction "1_1") (pintype "passive"))
      (node (ref "J1") (pin "21") (pinfunction "21_21") (pintype "bidirectional"))
    )
    (net (code "38") (name "PREVGL") (class "Default")
      (node (ref "C11") (pin "1") (pinfunction "1_1") (pintype "passive"))
      (node (ref "D4") (pin "2") (pinfunction "A_2") (pintype "bidirectional"))
      (node (ref "J1") (pin "23") (pinfunction "23_23") (pintype "bidirectional"))
    )
    (net (code "39") (name "RESE") (class "Default")
      (node (ref "J1") (pin "3") (pinfunction "3_3") (pintype "bidirectional"))
      (node (ref "R3") (pin "1") (pinfunction "1_1") (pintype "passive"))
      (node (ref "_Q3") (pin "2") (pinfunction "S_2") (pintype "bidirectional"))
    )
    (net (code "40") (name "RESE'") (class "Default")
      (node (ref "R2") (pin "2") (pinfunction "2_2") (pintype "passive"))
      (node (ref "R3") (pin "2") (pinfunction "2_2") (pintype "passive"))
      (node (ref "SJ1") (pin "2") (pinfunction "2_2") (pintype "passive"))
    )
    (net (code "41") (name "RESET") (class "Default")
      (node (ref "C5") (pin "1") (pinfunction "1_1") (pintype "passive"))
      (node (ref "IC2") (pin "1") (pinfunction "VOUT_1") (pintype "bidirectional"))
      (node (ref "RESET_BUTTON") (pin "3") (pinfunction "3_3") (pintype "passive"))
      (node (ref "RESET_BUTTON") (pin "4") (pinfunction "4_4") (pintype "passive"))
      (node (ref "R_RESET") (pin "2") (pinfunction "2_2") (pintype "passive"))
      (node (ref "U2") (pin "3") (pinfunction "EN_3") (pintype "input"))
    )
    (net (code "42") (name "RTC_RST") (class "Default")
      (node (ref "U2") (pin "16") (pinfunction "IO18_16") (pintype "bidirectional"))
      (node (ref "U3") (pin "4") (pinfunction "~{RST}_4") (pintype "input"))
    )
    (net (code "43") (name "RX") (class "Default")
      (node (ref "TP2") (pin "TP") (pinfunction "TP_TP") (pintype "input"))
      (node (ref "U2") (pin "24") (pinfunction "RXD0/GPIO17_24") (pintype "bidirectional"))
    )
    (net (code "44") (name "SCK") (class "Default")
      (node (ref "J1") (pin "13") (pinfunction "13_13") (pintype "bidirectional"))
      (node (ref "R6") (pin "1") (pinfunction "1_1") (pintype "passive"))
      (node (ref "TP8") (pin "TP") (pinfunction "TP_TP") (pintype "input"))
      (node (ref "U1") (pin "6") (pinfunction "CLK_6") (pintype "input"))
      (node (ref "U2") (pin "6") (pinfunction "IO6_6") (pintype "bidirectional"))
      (node (ref "_D10") (pin "2") (pinfunction "2_2") (pintype "passive"))
      (node (ref "_J4") (pin "P5") (pinfunction "CLK_P5") (pintype "bidirectional"))
    )
    (net (code "45") (name "SCL") (class "Default")
      (node (ref "J4") (pin "4") (pinfunction "4_4") (pintype "passive"))
      (node (ref "R2-PINH") (pin "1") (pinfunction "1_1") (pintype "passive"))
      (node (ref "SENSOR2") (pin "4") (pinfunction "SCK_4") (pintype "input"))
      (node (ref "U2") (pin "20") (pinfunction "IO22_20") (pintype "bidirectional"))
      (node (ref "U3") (pin "16") (pinfunction "SCL_16") (pintype "input"))
      (node (ref "U4") (pin "7") (pinfunction "SCL_7") (pintype "input"))
    )
    (net (code "46") (name "SDA") (class "Default")
      (node (ref "J4") (pin "3") (pinfunction "3_3") (pintype "passive"))
      (node (ref "R1-PINH") (pin "1") (pinfunction "1_1") (pintype "passive"))
      (node (ref "SENSOR2") (pin "3") (pinfunction "SDI_3") (pintype "bidirectional"))
      (node (ref "U2") (pin "19") (pinfunction "IO21_19") (pintype "bidirectional"))
      (node (ref "U3") (pin "15") (pinfunction "SDA_15") (pintype "bidirectional"))
      (node (ref "U4") (pin "8") (pinfunction "SDA_8") (pintype "bidirectional"))
    )
    (net (code "47") (name "SRC") (class "Default")
      (node (ref "C4") (pin "2") (pinfunction "2_2") (pintype "passive"))
      (node (ref "D5") (pin "2") (pinfunction "A_2") (pintype "bidirectional"))
      (node (ref "L1") (pin "1") (pinfunction "1_1") (pintype "passive"))
      (node (ref "_Q3") (pin "3") (pinfunction "D_3") (pintype "bidirectional"))
    )
    (net (code "48") (name "SS_SD") (class "Default")
      (node (ref "R10") (pin "1") (pinfunction "1_1") (pintype "passive"))
      (node (ref "U2") (pin "4") (pinfunction "IO4_4") (pintype "bidirectional"))
      (node (ref "_D8") (pin "2") (pinfunction "2_2") (pintype "passive"))
    )
    (net (code "49") (name "TX") (class "Default")
      (node (ref "TP1") (pin "TP") (pinfunction "TP_TP") (pintype "input"))
      (node (ref "U2") (pin "25") (pinfunction "TXD0/GPIO16_25") (pintype "bidirectional"))
    )
    (net (code "50") (name "USB_D+") (class "Default")
      (node (ref "D1") (pin "1") (pinfunction "I/O1_1_1") (pintype "bidirectional"))
      (node (ref "U2") (pin "14") (pinfunction "IO13_14") (pintype "bidirectional"))
    )
    (net (code "51") (name "USB_D-") (class "Default")
      (node (ref "D1") (pin "3") (pinfunction "I/O2_1_3") (pintype "bidirectional"))
      (node (ref "U2") (pin "13") (pinfunction "IO12_13") (pintype "bidirectional"))
    )
    (net (code "52") (name "VBAT") (class "Default")
      (node (ref "C2_BAT") (pin "1") (pinfunction "1_1") (pintype "passive"))
      (node (ref "MCP73831") (pin "3") (pinfunction "VBAT_3") (pintype "power_in"))
      (node (ref "Q1") (pin "3") (pinfunction "D_3") (pintype "bidirectional"))
      (node (ref "TP3") (pin "TP") (pinfunction "TP_TP") (pintype "input"))
      (node (ref "U4") (pin "2") (pinfunction "CELL_2") (pintype "power_in"))
      (node (ref "U4") (pin "3") (pinfunction "VDD_3") (pintype "power_in"))
    )
    (net (code "53") (name "VBUS") (class "Default")
      (node (ref "C1_BAT") (pin "1") (pinfunction "1_1") (pintype "passive"))
      (node (ref "C4_USB") (pin "1") (pinfunction "1_1") (pintype "passive"))
      (node (ref "C5_USB") (pin "1") (pinfunction "1_1") (pintype "passive"))
      (node (ref "CHG_LED") (pin "A") (pinfunction "A_A") (pintype "passive"))
      (node (ref "D1") (pin "5") (pinfunction "VBUS_5") (pintype "bidirectional"))
      (node (ref "D2") (pin "2") (pinfunction "ANODE_2") (pintype "bidirectional"))
      (node (ref "MCP73831") (pin "4") (pinfunction "VIN_4") (pintype "power_in"))
      (node (ref "PFMF.050.1") (pin "2") (pinfunction "2_2") (pintype "passive"))
      (node (ref "Q1") (pin "1") (pinfunction "G_1") (pintype "bidirectional"))
      (node (ref "R1_PWRUSB") (pin "2") (pinfunction "2_2") (pintype "passive"))
      (node (ref "TP14") (pin "TP") (pinfunction "TP_TP") (pintype "input"))
    )
    (net (code "54") (name "VRTC") (class "Default")
      (node (ref "C10_SUPERCAP") (pin "2") (pinfunction "2_2") (pintype "passive"))
      (node (ref "C8") (pin "1") (pinfunction "1_1") (pintype "passive"))
      (node (ref "R_CAPACITOR") (pin "1") (pinfunction "1_1") (pintype "passive"))
      (node (ref "U3") (pin "14") (pinfunction "VBAT_14") (pintype "power_in"))
    )
    (net (code "55") (name "VUSB") (class "Default")
      (node (ref "PFMF.050.1") (pin "1") (pinfunction "1_1") (pintype "passive"))
      (node (ref "_J2") (pin "A4") (pinfunction "A4_A4") (pintype "bidirectional"))
      (node (ref "_J2") (pin "A9") (pinfunction "A9_A9") (pintype "bidirectional"))
      (node (ref "_J2") (pin "B4") (pinfunction "B4_B4") (pintype "bidirectional"))
      (node (ref "_J2") (pin "B9") (pinfunction "B9_B9") (pintype "bidirectional"))
    )
    (net (code "56") (name "unconnected-(IC2-NC-Pad4)") (class "Default")
      (node (ref "IC2") (pin "4") (pinfunction "NC_4") (pintype "no_connect"))
    )
    (net (code "57") (name "unconnected-(IC4-NC-Pad4)") (class "Default")
      (node (ref "IC4") (pin "4") (pinfunction "NC_4") (pintype "no_connect"))
    )
    (net (code "58") (name "unconnected-(J1-Pad1)") (class "Default")
      (node (ref "J1") (pin "1") (pinfunction "1_1") (pintype "bidirectional"))
    )
    (net (code "59") (name "unconnected-(J1-Pad6)") (class "Default")
      (node (ref "J1") (pin "6") (pinfunction "6_6") (pintype "bidirectional"))
    )
    (net (code "60") (name "unconnected-(J1-Pad7)") (class "Default")
      (node (ref "J1") (pin "7") (pinfunction "7_7") (pintype "bidirectional"))
    )
    (net (code "61") (name "unconnected-(U2-NC-Pad22)") (class "Default")
      (node (ref "U2") (pin "22") (pinfunction "NC_22") (pintype "no_connect"))
    )
    (net (code "62") (name "unconnected-(U4-~{ALERT}-Pad5)") (class "Default")
      (node (ref "U4") (pin "5") (pinfunction "~{ALERT}_5") (pintype "output"))
    )
    (net (code "63") (name "unconnected-(_J2-PadA8)") (class "Default")
      (node (ref "_J2") (pin "A8") (pinfunction "A8_A8") (pintype "bidirectional"))
    )
    (net (code "64") (name "unconnected-(_J2-PadB8)") (class "Default")
      (node (ref "_J2") (pin "B8") (pinfunction "B8_B8") (pintype "bidirectional"))
    )
    (net (code "65") (name "unconnected-(_J4-CD{slash}DAT3-PadP2)") (class "Default")
      (node (ref "_J4") (pin "P2") (pinfunction "CD/DAT3_P2") (pintype "bidirectional"))
    )
    (net (code "66") (name "unconnected-(_J4-CMD-PadP3)") (class "Default")
      (node (ref "_J4") (pin "P3") (pinfunction "CMD_P3") (pintype "bidirectional"))
    )
    (net (code "67") (name "unconnected-(_J4-DAT1-PadP8)") (class "Default")
      (node (ref "_J4") (pin "P8") (pinfunction "DAT1_P8") (pintype "bidirectional"))
    )
    (net (code "68") (name "unconnected-(_J4-DAT2-PadP1)") (class "Default")
      (node (ref "_J4") (pin "P1") (pinfunction "DAT2_P1") (pintype "bidirectional"))
    )
    (net (code "69") (name "unconnected-(_J4-DETECTION_1-PadS1)") (class "Default")
      (node (ref "_J4") (pin "S1") (pinfunction "DETECTION_1_S1") (pintype "bidirectional"))
    )
    (net (code "70") (name "unconnected-(_J4-DETECTION_2-PadS2)") (class "Default")
      (node (ref "_J4") (pin "S2") (pinfunction "DETECTION_2_S2") (pintype "bidirectional"))
    )
  )
)
